# CMSIS-DAP_V2.net
KiCad netlist of a schematic drawn in EAGLE
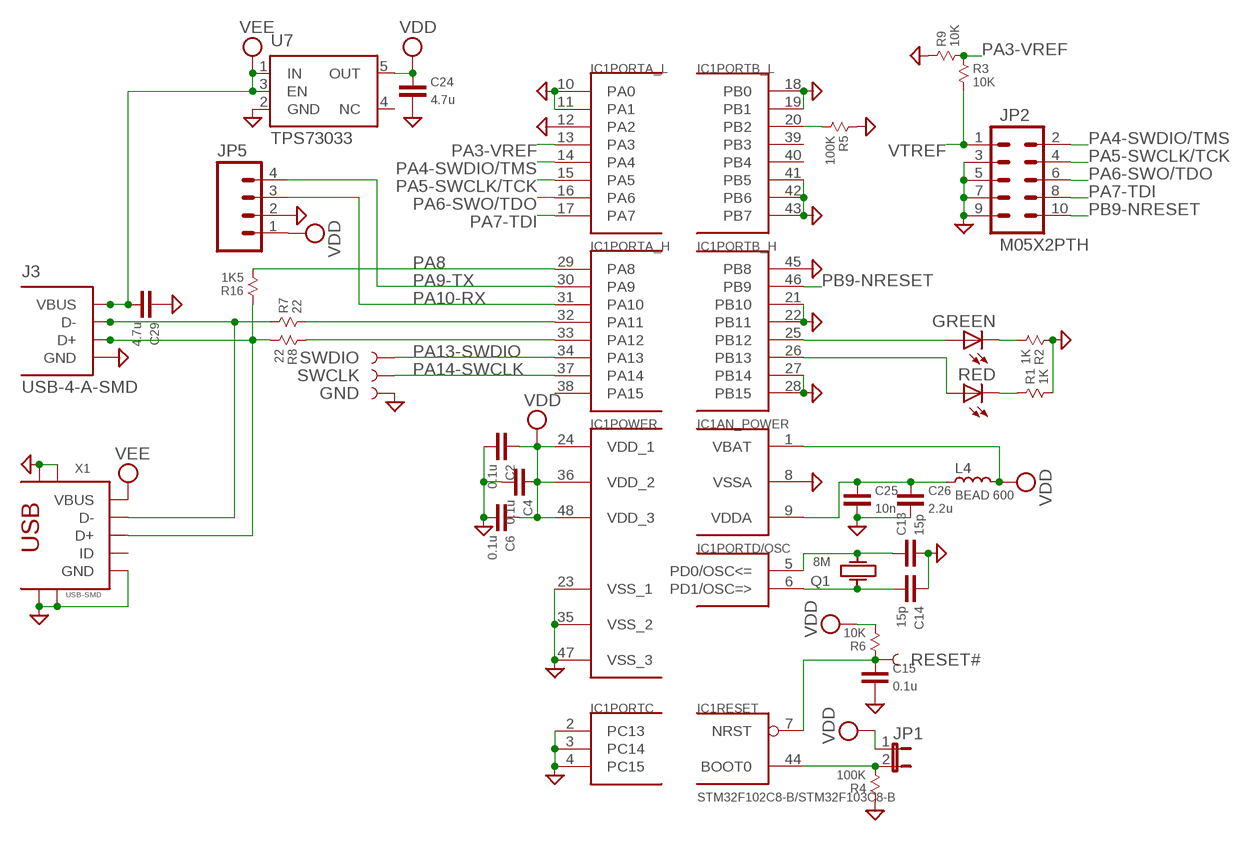
[diagram p0: schematic, sheet 1]

(export (version "E")
  (design (tool "Eeschema 10.0.6"))
  (components
    (comp (ref "C2")
      (value "0.1u")
      (footprint "eagle-import:0603")
      (libsource (lib "eagle-import") (part "CAP-0603"))
    )
    (comp (ref "C4")
      (value "0.1u")
      (footprint "eagle-import:0603")
      (libsource (lib "eagle-import") (part "CAP-0603"))
    )
    (comp (ref "C6")
      (value "0.1u")
      (footprint "eagle-import:0603")
      (libsource (lib "eagle-import") (part "CAP-0603"))
    )
    (comp (ref "C13")
      (value "15p")
      (footprint "eagle-import:0603")
      (libsource (lib "eagle-import") (part "CAP-0603"))
    )
    (comp (ref "C14")
      (value "15p")
      (footprint "eagle-import:0603")
      (libsource (lib "eagle-import") (part "CAP-0603"))
    )
    (comp (ref "C15")
      (value "0.1u")
      (footprint "eagle-import:0603")
      (libsource (lib "eagle-import") (part "CAP-0603"))
    )
    (comp (ref "C24")
      (value "4.7u")
      (footprint "eagle-import:0603")
      (libsource (lib "eagle-import") (part "CAP-0603"))
    )
    (comp (ref "C25")
      (value "10n")
      (footprint "eagle-import:0603")
      (libsource (lib "eagle-import") (part "CAP-0603"))
    )
    (comp (ref "C26")
      (value "2.2u")
      (footprint "eagle-import:0603")
      (libsource (lib "eagle-import") (part "CAP-0603"))
    )
    (comp (ref "C29")
      (value "4.7u")
      (footprint "eagle-import:0603")
      (libsource (lib "eagle-import") (part "CAP-0603"))
    )
    (comp (ref "GND")
      (value "TEST-POINT1")
      (footprint "eagle-import:PAD.1X1")
      (libsource (lib "eagle-import") (part "TEST-POINT1"))
    )
    (comp (ref "GREEN")
      (value "LEDCHIPLED_0603")
      (footprint "eagle-import:CHIPLED_0603")
      (libsource (lib "eagle-import") (part "LEDCHIPLED_0603"))
    )
    (comp (ref "IC1")
      (value "STM32F102C8-B/STM32F103C8-B")
      (footprint "eagle-import:TQFP48")
      (libsource (lib "eagle-import") (part "STM32F10XCXT6"))
    )
    (comp (ref "J3")
      (value "USB-4-A-SMD")
      (footprint "eagle-import:USB-A-SMD")
      (libsource (lib "eagle-import") (part "USB-4-A-SMD"))
    )
    (comp (ref "JP1")
      (value "JUMPER-2SMD-NO")
      (footprint "eagle-import:SJ_2S-NO")
      (libsource (lib "eagle-import") (part "JUMPER-2SMD-NO"))
    )
    (comp (ref "JP2")
      (value "M05X2PTH")
      (footprint "eagle-import:AVR_ICSP")
      (libsource (lib "eagle-import") (part "M05X2PTH"))
    )
    (comp (ref "JP5")
      (value "M04PTH")
      (footprint "eagle-import:1X04")
      (libsource (lib "eagle-import") (part "M04PTH"))
    )
    (comp (ref "L4")
      (value "BEAD 600")
      (footprint "eagle-import:0603")
      (libsource (lib "eagle-import") (part "INDUCTOR-0603"))
    )
    (comp (ref "Q1")
      (value "8M")
      (footprint "eagle-import:KX-9A")
      (libsource (lib "eagle-import") (part "CRYSTAL-KX-9A"))
    )
    (comp (ref "R1")
      (value "1K")
      (footprint "eagle-import:0603")
      (libsource (lib "eagle-import") (part "RESISTOR-0603"))
    )
    (comp (ref "R2")
      (value "1K")
      (footprint "eagle-import:0603")
      (libsource (lib "eagle-import") (part "RESISTOR-0603"))
    )
    (comp (ref "R3")
      (value "10K")
      (footprint "eagle-import:0603")
      (libsource (lib "eagle-import") (part "RESISTOR-0603"))
    )
    (comp (ref "R4")
      (value "100K")
      (footprint "eagle-import:0603")
      (libsource (lib "eagle-import") (part "RESISTOR-0603"))
    )
    (comp (ref "R5")
      (value "100K")
      (footprint "eagle-import:0603")
      (libsource (lib "eagle-import") (part "RESISTOR-0603"))
    )
    (comp (ref "R6")
      (value "10K")
      (footprint "eagle-import:0603")
      (libsource (lib "eagle-import") (part "RESISTOR-0603"))
    )
    (comp (ref "R7")
      (value "22")
      (footprint "eagle-import:0603")
      (libsource (lib "eagle-import") (part "RESISTOR-0603"))
    )
    (comp (ref "R8")
      (value "22")
      (footprint "eagle-import:0603")
      (libsource (lib "eagle-import") (part "RESISTOR-0603"))
    )
    (comp (ref "R9")
      (value "10K")
      (footprint "eagle-import:0603")
      (libsource (lib "eagle-import") (part "RESISTOR-0603"))
    )
    (comp (ref "R16")
      (value "1K5")
      (footprint "eagle-import:0603")
      (libsource (lib "eagle-import") (part "RESISTOR-0603"))
    )
    (comp (ref "RED")
      (value "LEDCHIPLED_0603")
      (footprint "eagle-import:CHIPLED_0603")
      (libsource (lib "eagle-import") (part "LEDCHIPLED_0603"))
    )
    (comp (ref "RESET#")
      (value "TEST-POINT3")
      (footprint "eagle-import:PAD.03X.03")
      (libsource (lib "eagle-import") (part "TEST-POINT3"))
    )
    (comp (ref "SWCLK")
      (value "TEST-POINT1")
      (footprint "eagle-import:PAD.1X1")
      (libsource (lib "eagle-import") (part "TEST-POINT1"))
    )
    (comp (ref "SWDIO")
      (value "TEST-POINT1")
      (footprint "eagle-import:PAD.1X1")
      (libsource (lib "eagle-import") (part "TEST-POINT1"))
    )
    (comp (ref "U7")
      (value "TPS73033")
      (footprint "eagle-import:SOT23-5")
      (libsource (lib "eagle-import") (part "TPS73033"))
    )
    (comp (ref "X1")
      (value "USB-SMD")
      (footprint "eagle-import:USB-MINIB")
      (libsource (lib "eagle-import") (part "USB-SMD"))
    )
  )
  (nets
    (net (code "1") (name "/PA3-VREF") (class "Default")
      (node (ref "IC1") (pin "13") (pinfunction "PA3_13") (pintype "bidirectional"))
      (node (ref "R3") (pin "1") (pinfunction "1_1") (pintype "passive"))
      (node (ref "R9") (pin "2") (pinfunction "2_2") (pintype "passive"))
    )
    (net (code "2") (name "/PA4-SWDIO{slash}TMS") (class "Default")
      (node (ref "IC1") (pin "14") (pinfunction "PA4_14") (pintype "bidirectional"))
      (node (ref "JP2") (pin "2") (pinfunction "2_2") (pintype "passive"))
    )
    (net (code "3") (name "/PA5-SWCLK{slash}TCK") (class "Default")
      (node (ref "IC1") (pin "15") (pinfunction "PA5_15") (pintype "bidirectional"))
      (node (ref "JP2") (pin "4") (pinfunction "4_4") (pintype "passive"))
    )
    (net (code "4") (name "/PA6-SWO{slash}TDO") (class "Default")
      (node (ref "IC1") (pin "16") (pinfunction "PA6_16") (pintype "bidirectional"))
      (node (ref "JP2") (pin "6") (pinfunction "6_6") (pintype "passive"))
    )
    (net (code "5") (name "/PA7-TDI") (class "Default")
      (node (ref "IC1") (pin "17") (pinfunction "PA7_17") (pintype "bidirectional"))
      (node (ref "JP2") (pin "8") (pinfunction "8_8") (pintype "passive"))
    )
    (net (code "6") (name "/PA8") (class "Default")
      (node (ref "IC1") (pin "29") (pinfunction "PA8_29") (pintype "bidirectional"))
      (node (ref "R16") (pin "2") (pinfunction "2_2") (pintype "passive"))
    )
    (net (code "7") (name "/PA9-TX") (class "Default")
      (node (ref "IC1") (pin "30") (pinfunction "PA9_30") (pintype "bidirectional"))
      (node (ref "JP5") (pin "4") (pinfunction "4_4") (pintype "passive"))
    )
    (net (code "8") (name "/PA10-RX") (class "Default")
      (node (ref "IC1") (pin "31") (pinfunction "PA10_31") (pintype "bidirectional"))
      (node (ref "JP5") (pin "3") (pinfunction "3_3") (pintype "passive"))
    )
    (net (code "9") (name "/PA13-SWDIO") (class "Default")
      (node (ref "IC1") (pin "34") (pinfunction "PA13_34") (pintype "bidirectional"))
      (node (ref "SWDIO") (pin "P$1") (pinfunction "1_P$1") (pintype "bidirectional"))
    )
    (net (code "10") (name "/PA14-SWCLK") (class "Default")
      (node (ref "IC1") (pin "37") (pinfunction "PA14_37") (pintype "bidirectional"))
      (node (ref "SWCLK") (pin "P$1") (pinfunction "1_P$1") (pintype "bidirectional"))
    )
    (net (code "11") (name "/PB9-NRESET") (class "Default")
      (node (ref "IC1") (pin "46") (pinfunction "PB9_46") (pintype "bidirectional"))
      (node (ref "JP2") (pin "10") (pinfunction "10_10") (pintype "passive"))
    )
    (net (code "12") (name "/VTREF") (class "Default")
      (node (ref "JP2") (pin "1") (pinfunction "1_1") (pintype "passive"))
      (node (ref "R3") (pin "2") (pinfunction "2_2") (pintype "passive"))
    )
    (net (code "13") (name "GND") (class "Default")
      (node (ref "C13") (pin "1") (pinfunction "1_1") (pintype "passive"))
      (node (ref "C14") (pin "2") (pinfunction "2_2") (pintype "passive"))
      (node (ref "C15") (pin "1") (pinfunction "1_1") (pintype "passive"))
      (node (ref "C2") (pin "1") (pinfunction "1_1") (pintype "passive"))
      (node (ref "C24") (pin "1") (pinfunction "1_1") (pintype "passive"))
      (node (ref "C25") (pin "1") (pinfunction "1_1") (pintype "passive"))
      (node (ref "C26") (pin "1") (pinfunction "1_1") (pintype "passive"))
      (node (ref "C29") (pin "2") (pinfunction "2_2") (pintype "passive"))
      (node (ref "C4") (pin "1") (pinfunction "1_1") (pintype "passive"))
      (node (ref "C6") (pin "1") (pinfunction "1_1") (pintype "passive"))
      (node (ref "GND") (pin "P$1") (pinfunction "1_P$1") (pintype "bidirectional"))
      (node (ref "IC1") (pin "10") (pinfunction "PA0_10") (pintype "bidirectional"))
      (node (ref "IC1") (pin "11") (pinfunction "PA1_11") (pintype "bidirectional"))
      (node (ref "IC1") (pin "12") (pinfunction "PA2_12") (pintype "bidirectional"))
      (node (ref "IC1") (pin "18") (pinfunction "PB0_18") (pintype "bidirectional"))
      (node (ref "IC1") (pin "19") (pinfunction "PB1_19") (pintype "bidirectional"))
      (node (ref "IC1") (pin "2") (pinfunction "PC13_2") (pintype "bidirectional"))
      (node (ref "IC1") (pin "21") (pinfunction "PB10_21") (pintype "bidirectional"))
      (node (ref "IC1") (pin "22") (pinfunction "PB11_22") (pintype "bidirectional"))
      (node (ref "IC1") (pin "23") (pinfunction "VSS_1_23") (pintype "power_in"))
      (node (ref "IC1") (pin "27") (pinfunction "PB14_27") (pintype "bidirectional"))
      (node (ref "IC1") (pin "28") (pinfunction "PB15_28") (pintype "bidirectional"))
      (node (ref "IC1") (pin "3") (pinfunction "PC14_3") (pintype "bidirectional"))
      (node (ref "IC1") (pin "35") (pinfunction "VSS_2_35") (pintype "power_in"))
      (node (ref "IC1") (pin "4") (pinfunction "PC15_4") (pintype "bidirectional"))
      (node (ref "IC1") (pin "41") (pinfunction "PB5_41") (pintype "bidirectional"))
      (node (ref "IC1") (pin "42") (pinfunction "PB6_42") (pintype "bidirectional"))
      (node (ref "IC1") (pin "43") (pinfunction "PB7_43") (pintype "bidirectional"))
      (node (ref "IC1") (pin "45") (pinfunction "PB8_45") (pintype "bidirectional"))
      (node (ref "IC1") (pin "47") (pinfunction "VSS_3_47") (pintype "power_in"))
      (node (ref "IC1") (pin "8") (pinfunction "VSSA_8") (pintype "power_in"))
      (node (ref "J3") (pin "GND") (pinfunction "GND_GND") (pintype "power_in"))
      (node (ref "JP2") (pin "3") (pinfunction "3_3") (pintype "passive"))
      (node (ref "JP2") (pin "5") (pinfunction "5_5") (pintype "passive"))
      (node (ref "JP2") (pin "7") (pinfunction "7_7") (pintype "passive"))
      (node (ref "JP2") (pin "9") (pinfunction "9_9") (pintype "passive"))
      (node (ref "JP5") (pin "2") (pinfunction "2_2") (pintype "passive"))
      (node (ref "R1") (pin "2") (pinfunction "2_2") (pintype "passive"))
      (node (ref "R2") (pin "1") (pinfunction "1_1") (pintype "passive"))
      (node (ref "R4") (pin "1") (pinfunction "1_1") (pintype "passive"))
      (node (ref "R5") (pin "1") (pinfunction "1_1") (pintype "passive"))
      (node (ref "R9") (pin "1") (pinfunction "1_1") (pintype "passive"))
      (node (ref "U7") (pin "2") (pinfunction "GND_2") (pintype "power_in"))
      (node (ref "X1") (pin "GND") (pinfunction "GND_GND") (pintype "power_in"))
      (node (ref "X1") (pin "GND@1") (pinfunction "GND_GND@1") (pintype "power_in"))
      (node (ref "X1") (pin "GND@2") (pinfunction "GND_GND@2") (pintype "power_in"))
      (node (ref "X1") (pin "GND@3") (pinfunction "GND_GND@3") (pintype "power_in"))
      (node (ref "X1") (pin "GND@4") (pinfunction "GND_GND@4") (pintype "power_in"))
    )
    (net (code "14") (name "Net-(GREEN-PadC)") (class "Default")
      (node (ref "GREEN") (pin "C") (pinfunction "C_C") (pintype "passive"))
      (node (ref "R2") (pin "2") (pinfunction "2_2") (pintype "passive"))
    )
    (net (code "15") (name "Net-(IC1A-VDDA)") (class "Default")
      (node (ref "C25") (pin "2") (pinfunction "2_2") (pintype "passive"))
      (node (ref "C26") (pin "2") (pinfunction "2_2") (pintype "passive"))
      (node (ref "IC1") (pin "9") (pinfunction "VDDA_9") (pintype "power_in"))
      (node (ref "L4") (pin "1") (pinfunction "1_1") (pintype "passive"))
    )
    (net (code "16") (name "Net-(IC1B-PA11)") (class "Default")
      (node (ref "IC1") (pin "32") (pinfunction "PA11_32") (pintype "bidirectional"))
      (node (ref "R7") (pin "2") (pinfunction "2_2") (pintype "passive"))
    )
    (net (code "17") (name "Net-(IC1B-PA12)") (class "Default")
      (node (ref "IC1") (pin "33") (pinfunction "PA12_33") (pintype "bidirectional"))
      (node (ref "R8") (pin "1") (pinfunction "1_1") (pintype "passive"))
    )
    (net (code "18") (name "Net-(IC1D-PB12)") (class "Default")
      (node (ref "GREEN") (pin "A") (pinfunction "A_A") (pintype "passive"))
      (node (ref "IC1") (pin "25") (pinfunction "PB12_25") (pintype "bidirectional"))
    )
    (net (code "19") (name "Net-(IC1D-PB13)") (class "Default")
      (node (ref "IC1") (pin "26") (pinfunction "PB13_26") (pintype "bidirectional"))
      (node (ref "RED") (pin "A") (pinfunction "A_A") (pintype "passive"))
    )
    (net (code "20") (name "Net-(IC1E-PB2)") (class "Default")
      (node (ref "IC1") (pin "20") (pinfunction "PB2_20") (pintype "bidirectional"))
      (node (ref "R5") (pin "2") (pinfunction "2_2") (pintype "passive"))
    )
    (net (code "21") (name "Net-(IC1G-PD0{slash}OSC<=)") (class "Default")
      (node (ref "C13") (pin "2") (pinfunction "2_2") (pintype "passive"))
      (node (ref "IC1") (pin "5") (pinfunction "PD0/OSC<=_5") (pintype "bidirectional"))
      (node (ref "Q1") (pin "3") (pinfunction "2_3") (pintype "passive"))
    )
    (net (code "22") (name "Net-(IC1G-PD1{slash}OSC=>)") (class "Default")
      (node (ref "C14") (pin "1") (pinfunction "1_1") (pintype "passive"))
      (node (ref "IC1") (pin "6") (pinfunction "PD1/OSC=>_6") (pintype "bidirectional"))
      (node (ref "Q1") (pin "1") (pinfunction "1_1") (pintype "passive"))
    )
    (net (code "23") (name "Net-(IC1I-BOOT0)") (class "Default")
      (node (ref "IC1") (pin "44") (pinfunction "BOOT0_44") (pintype "input"))
      (node (ref "JP1") (pin "2") (pinfunction "2_2") (pintype "passive"))
      (node (ref "R4") (pin "2") (pinfunction "2_2") (pintype "passive"))
    )
    (net (code "24") (name "Net-(IC1I-NRST)") (class "Default")
      (node (ref "C15") (pin "2") (pinfunction "2_2") (pintype "passive"))
      (node (ref "IC1") (pin "7") (pinfunction "NRST_7") (pintype "input"))
      (node (ref "R6") (pin "1") (pinfunction "1_1") (pintype "passive"))
      (node (ref "RESET#") (pin "P$1") (pinfunction "1_P$1") (pintype "bidirectional"))
    )
    (net (code "25") (name "Net-(J3-PadD+)") (class "Default")
      (node (ref "J3") (pin "D+") (pinfunction "D+_D+") (pintype "bidirectional"))
      (node (ref "R16") (pin "1") (pinfunction "1_1") (pintype "passive"))
      (node (ref "R8") (pin "2") (pinfunction "2_2") (pintype "passive"))
      (node (ref "X1") (pin "D+") (pinfunction "D+_D+") (pintype "bidirectional"))
    )
    (net (code "26") (name "Net-(J3-PadD-)") (class "Default")
      (node (ref "J3") (pin "D-") (pinfunction "D-_D-") (pintype "bidirectional"))
      (node (ref "R7") (pin "1") (pinfunction "1_1") (pintype "passive"))
      (node (ref "X1") (pin "D-") (pinfunction "D-_D-") (pintype "bidirectional"))
    )
    (net (code "27") (name "Net-(R1-Pad1)") (class "Default")
      (node (ref "R1") (pin "1") (pinfunction "1_1") (pintype "passive"))
      (node (ref "RED") (pin "C") (pinfunction "C_C") (pintype "passive"))
    )
    (net (code "28") (name "VDD") (class "Default")
      (node (ref "C2") (pin "2") (pinfunction "2_2") (pintype "passive"))
      (node (ref "C24") (pin "2") (pinfunction "2_2") (pintype "passive"))
      (node (ref "C4") (pin "2") (pinfunction "2_2") (pintype "passive"))
      (node (ref "C6") (pin "2") (pinfunction "2_2") (pintype "passive"))
      (node (ref "IC1") (pin "1") (pinfunction "VBAT_1") (pintype "power_in"))
      (node (ref "IC1") (pin "24") (pinfunction "VDD_1_24") (pintype "power_in"))
      (node (ref "IC1") (pin "36") (pinfunction "VDD_2_36") (pintype "power_in"))
      (node (ref "IC1") (pin "48") (pinfunction "VDD_3_48") (pintype "power_in"))
      (node (ref "JP1") (pin "1") (pinfunction "1_1") (pintype "passive"))
      (node (ref "JP5") (pin "1") (pinfunction "1_1") (pintype "passive"))
      (node (ref "L4") (pin "2") (pinfunction "2_2") (pintype "passive"))
      (node (ref "R6") (pin "2") (pinfunction "2_2") (pintype "passive"))
      (node (ref "U7") (pin "5") (pinfunction "OUT_5") (pintype "passive"))
    )
    (net (code "29") (name "VEE") (class "Default")
      (node (ref "C29") (pin "1") (pinfunction "1_1") (pintype "passive"))
      (node (ref "J3") (pin "VUSB") (pinfunction "VBUS_VUSB") (pintype "passive"))
      (node (ref "U7") (pin "1") (pinfunction "IN_1") (pintype "passive"))
      (node (ref "U7") (pin "3") (pinfunction "EN_3") (pintype "input"))
      (node (ref "X1") (pin "VBUS") (pinfunction "VBUS_VBUS") (pintype "passive"))
    )
    (net (code "30") (name "unconnected-(IC1B-PA15-Pad38)") (class "Default")
      (node (ref "IC1") (pin "38") (pinfunction "PA15_38") (pintype "bidirectional"))
    )
    (net (code "31") (name "unconnected-(IC1E-PB3-Pad39)") (class "Default")
      (node (ref "IC1") (pin "39") (pinfunction "PB3_39") (pintype "bidirectional"))
    )
    (net (code "32") (name "unconnected-(IC1E-PB4-Pad40)") (class "Default")
      (node (ref "IC1") (pin "40") (pinfunction "PB4_40") (pintype "bidirectional"))
    )
    (net (code "33") (name "unconnected-(U7-NC-Pad4)") (class "Default")
      (node (ref "U7") (pin "4") (pinfunction "NC_4") (pintype "no_connect"))
    )
    (net (code "34") (name "unconnected-(X1-PadID)") (class "Default")
      (node (ref "X1") (pin "ID") (pinfunction "ID_ID") (pintype "bidirectional"))
    )
  )
)
